# Main.net
KiCad netlist of a schematic drawn in Altium Designer
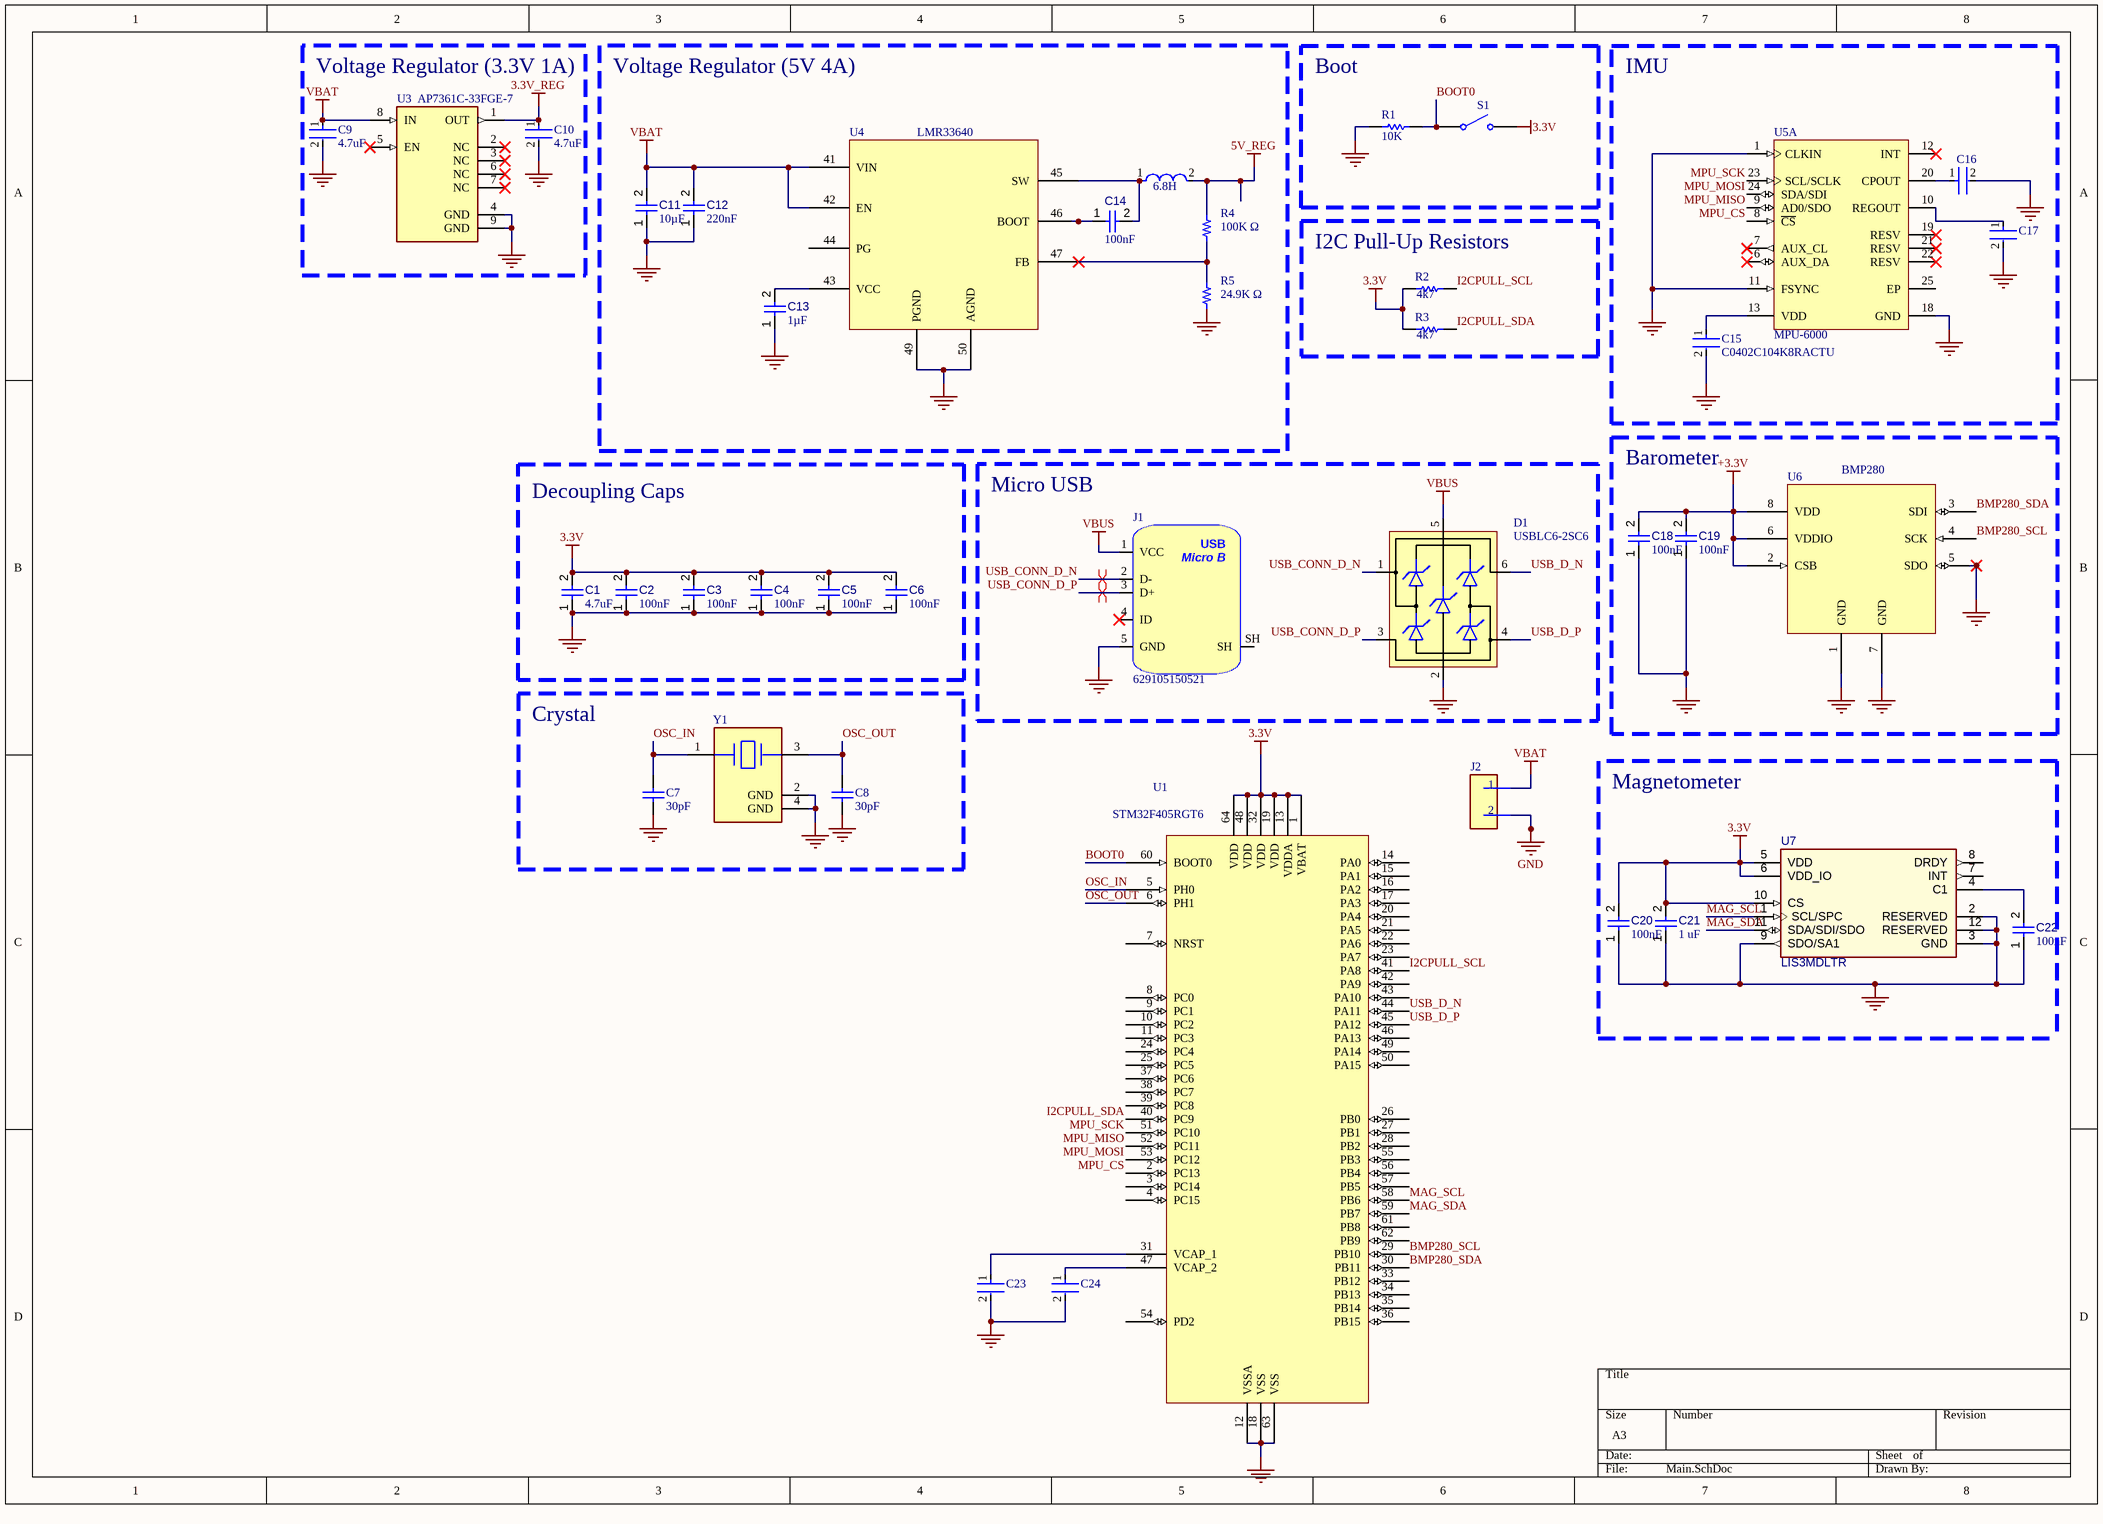
[diagram p0: Main.SchDoc]

(export (version "E")
  (design (tool "Eeschema 10.0.6"))
  (components
    (comp (ref "6.8H")
      (value "IHLP4040DZER6R8M01")
      (footprint "FP-IHLP-4040DZ-FP_3_124x3-MFG")
      (description "Commercial Inductors, High Saturation Series 6.8uH 8A 23.3mΩ 20%")
      (fields (field (name "TOLERANCE") "20%"))
      (libsource (lib "Altium Content Vault") (part "725321dda6339637d4d059423bc1c3c"))
    )
    (comp (ref "C1")
      (value "4.7uF")
      (footprint "CAPC1608X90X40NL10T20")
      (description "Chip Capacitor, 100 nF, +/- 10%, 50 V, 0603 (1608 Metric)")
      (fields (field (name "TOLERANCE") "10%") (field (name "Comment") "Capacitor 100 nF +/-10% 50 V 0603"))
      (libsource (lib "California Polytechnic University, Pomona") (part "CAP-NP-2"))
    )
    (comp (ref "C2")
      (value "100nF")
      (footprint "CAPC2013X95X50LL10T25")
      (description "Chip Capacitor, 100 nF, +/- 10%, 50 V, 0805 (2012 Metric)")
      (fields (field (name "TOLERANCE") "10%") (field (name "Comment") "Capacitor 100 nF +/-10% 50 V 0805"))
      (libsource (lib "California Polytechnic University, Pomona") (part "CAP-NP-2"))
    )
    (comp (ref "C3")
      (value "100nF")
      (footprint "CAPC2013X95X50LL10T25")
      (description "Chip Capacitor, 100 nF, +/- 10%, 50 V, 0805 (2012 Metric)")
      (fields (field (name "TOLERANCE") "10%") (field (name "Comment") "Capacitor 100 nF +/-10% 50 V 0805"))
      (libsource (lib "California Polytechnic University, Pomona") (part "CAP-NP-2"))
    )
    (comp (ref "C4")
      (value "100nF")
      (footprint "CAPC2013X95X50LL10T25")
      (description "Chip Capacitor, 100 nF, +/- 10%, 50 V, 0805 (2012 Metric)")
      (fields (field (name "TOLERANCE") "10%") (field (name "Comment") "Capacitor 100 nF +/-10% 50 V 0805"))
      (libsource (lib "California Polytechnic University, Pomona") (part "CAP-NP-2"))
    )
    (comp (ref "C5")
      (value "100nF")
      (footprint "CAPC2013X95X50LL10T25")
      (description "Chip Capacitor, 100 nF, +/- 10%, 50 V, 0805 (2012 Metric)")
      (fields (field (name "TOLERANCE") "10%") (field (name "Comment") "Capacitor 100 nF +/-10% 50 V 0805"))
      (libsource (lib "California Polytechnic University, Pomona") (part "CAP-NP-2"))
    )
    (comp (ref "C6")
      (value "100nF")
      (footprint "CAPC2013X95X50LL10T25")
      (description "Chip Capacitor, 100 nF, +/- 10%, 50 V, 0805 (2012 Metric)")
      (fields (field (name "TOLERANCE") "10%") (field (name "Comment") "Capacitor 100 nF +/-10% 50 V 0805"))
      (libsource (lib "California Polytechnic University, Pomona") (part "CAP-NP-2"))
    )
    (comp (ref "C7")
      (value "30pF")
      (footprint "CAPC1608X90X35NL10T15")
      (description "GRM1885C1H300JA01D")
      (fields (field (name "MANUFACTURER") "Murata"))
      (libsource (lib "Altium Content Vault") (part "CAP"))
    )
    (comp (ref "C8")
      (value "30pF")
      (footprint "CAPC1608X90X35NL10T15")
      (description "GRM1885C1H300JA01D")
      (fields (field (name "MANUFACTURER") "Murata"))
      (libsource (lib "Altium Content Vault") (part "CAP"))
    )
    (comp (ref "C9")
      (value "4.7uF")
      (footprint "FP-0805-L_2_01_0_2-W_1_25-IPC_A")
      (description "General Purpose Ceramic Capacitor, 0805, 4.7uF, 10%, X5R, 15%, 16V")
      (fields (field (name "TOLERANCE") "10%"))
      (libsource (lib "Altium Content Vault") (part "b4654b650e69147ec39a6b967a45e02"))
    )
    (comp (ref "C10")
      (value "4.7uF")
      (footprint "FP-0805-L_2_01_0_2-W_1_25-IPC_A")
      (description "General Purpose Ceramic Capacitor, 0805, 4.7uF, 10%, X5R, 15%, 16V")
      (fields (field (name "TOLERANCE") "10%"))
      (libsource (lib "Altium Content Vault") (part "b4654b650e69147ec39a6b967a45e02"))
    )
    (comp (ref "C11")
      (value "10µF")
      (footprint "CAPC0603(1608)100_L")
      (description "Chip Capacitor, 10µF +/-20%, 10V, 0603, Thickness 1 mm")
      (fields (field (name "TOLERANCE") "10%") (field (name "Comment") "Capacitor 10µF +/-20% 10V 0603"))
      (libsource (lib "California Polytechnic University, Pomona") (part "CAP-NP-2"))
    )
    (comp (ref "C12")
      (value "220nF")
      (footprint "CAPC0402(1005)60_L")
      (description "Chip Capacitor, 220nF +/-20%, 10V, 0402, Thickness 0.6 mm")
      (fields (field (name "TOLERANCE") "10%") (field (name "Comment") "Capacitor 220nF +/-20% 10V 0402"))
      (libsource (lib "California Polytechnic University, Pomona") (part "CAP-NP-2"))
    )
    (comp (ref "C13")
      (value "1µF")
      (footprint "CAPC1608X90X35ML15T15")
      (description "Chip Capacitor, 1 uF, +/- 10%, 16 V, 0603 (1608 Metric)")
      (fields (field (name "TOLERANCE") "10%") (field (name "Comment") "Capacitor 1uF +/- 10% 16V 0603"))
      (libsource (lib "California Polytechnic University, Pomona") (part "CAP-NP-2"))
    )
    (comp (ref "C14")
      (value "100nF")
      (footprint "CAPC1005X56X25LL10T15")
      (description "Chip Capacitor, 0.1 uF, +/- 5%, 16 V, 0402 (1005 Metric)")
      (fields (field (name "TOLERANCE") "5%") (field (name "Comment") "Capacitor 0.1 uF +/- 5% 16 V 0402"))
      (libsource (lib "California Polytechnic University, Pomona") (part "CAP-NP-2"))
    )
    (comp (ref "C15")
      (value "C0402C104K8RACTU")
      (footprint "FP-C0402-BB-MFG")
      (description "CAP CER 0.1UF 10V X7R 0402")
      (fields
        (field (name "OCTOPART") "https://octopart.com/c0402c104k8ractu-kemet-106349")
        (field (name "TOLERANCE") "0.1")
      )
      (libsource (lib "Altium Content Vault") (part "b4654b650e69147ec39a6b967a45e02"))
    )
    (comp (ref "C16")
      (value "06035C222KAT2A")
      (footprint "FP-0603-L_1_6_0_15-W_0_81-IPC_C")
      (description "General Purpose Ceramic Capacitor, 0603, 2.2nF, 10%, X7R, 15%, 50V")
      (fields (field (name "TOLERANCE") "10%") (field (name "VOLTAGE") "25V"))
      (libsource (lib "Altium Content Vault") (part "02cd4be3c70576c341d710602a673aa"))
    )
    (comp (ref "C17")
      (value "C0402C104K8RACTU")
      (footprint "FP-C0402-BB-MFG")
      (description "CAP CER 0.1UF 10V X7R 0402")
      (fields
        (field (name "OCTOPART") "https://octopart.com/c0402c104k8ractu-kemet-106349")
        (field (name "TOLERANCE") "0.1")
      )
      (libsource (lib "Altium Content Vault") (part "b4654b650e69147ec39a6b967a45e02"))
    )
    (comp (ref "C18")
      (value "100nF")
      (footprint "CAPC1005X56X25LL10T15")
      (description "Ceramic, X7R, +-10%, 2V")
      (fields (field (name "TOLERANCE") "5%") (field (name "Comment") "Capacitor 0.1 uF +/- 5% 16 V 0402"))
      (libsource (lib "California Polytechnic University, Pomona") (part "CAP-NP-2"))
    )
    (comp (ref "C19")
      (value "100nF")
      (footprint "CAPC1005X56X25LL10T15")
      (description "Ceramic, X7R, +-10%, 2V")
      (fields (field (name "TOLERANCE") "5%") (field (name "Comment") "Capacitor 0.1 uF +/- 5% 16 V 0402"))
      (libsource (lib "California Polytechnic University, Pomona") (part "CAP-NP-2"))
    )
    (comp (ref "C20")
      (value "100nF")
      (footprint "CAPC1005X56X25LL10T15")
      (description "Ceramic, X7R, +-10%, 2V")
      (fields (field (name "TOLERANCE") "5%") (field (name "Comment") "Capacitor 0.1 uF +/- 5% 16 V 0402"))
      (libsource (lib "California Polytechnic University, Pomona") (part "CAP-NP-2"))
    )
    (comp (ref "C21")
      (value "1 uF")
      (footprint "CAPC1005X56X25LL10T15")
      (description "Electrolytic Cap")
      (fields (field (name "TOLERANCE") "5%") (field (name "Comment") "Capacitor 0.1 uF +/- 5% 16 V 0402"))
      (libsource (lib "California Polytechnic University, Pomona") (part "CAP-NP-2"))
    )
    (comp (ref "C22")
      (value "100nF")
      (footprint "CAPC1005X56X25LL10T15")
      (description "Ceramic, X7R, +-10%, 2V")
      (fields (field (name "TOLERANCE") "5%") (field (name "Comment") "Capacitor 0.1 uF +/- 5% 16 V 0402"))
      (libsource (lib "California Polytechnic University, Pomona") (part "CAP-NP-2"))
    )
    (comp (ref "C23")
      (value "GCM21BR71A225KA37L")
      (footprint "FP-GCM21B-0_15-IPC_A")
      (description "Ceramic Capacitor for Automotive 2.2uF ±10% 10VDC X7R 0805 Embossed T/R")
      (fields (field (name "TOLERANCE") "10%") (field (name "VOLTAGE") "10V"))
      (libsource (lib "Altium Content Vault") (part "02cd4be3c70576c341d710602a673aa"))
    )
    (comp (ref "C24")
      (value "GCM21BR71A225KA37L")
      (footprint "FP-GCM21B-0_15-IPC_A")
      (description "Ceramic Capacitor for Automotive 2.2uF ±10% 10VDC X7R 0805 Embossed T/R")
      (fields (field (name "TOLERANCE") "10%") (field (name "VOLTAGE") "10V"))
      (libsource (lib "Altium Content Vault") (part "02cd4be3c70576c341d710602a673aa"))
    )
    (comp (ref "D1")
      (value "USBLC6-2SC6")
      (footprint "SOT-23-6")
      (description "Low-Capacitance ESD Protection USB")
      (fields (field (name "MANUFACTURER") "STMicroelectronics"))
      (libsource (lib "Schematic-Lib-PhilsLab") (part "USBLC6-2SC6"))
    )
    (comp (ref "J1")
      (value "629105150521")
      (footprint "629105150521")
      (description "USB Connector Type Micro B 2.0 SMD")
      (fields (field (name "MANUFACTURER") "Wurth"))
      (libsource (lib "Schematic-Lib-PhilsLab") (part "629105150521"))
    )
    (comp (ref "J2")
      (value "PRT-10474")
      (footprint "FP-PRT-10474-MFG")
      (description "XT60 CONNECTORS MALE/FEMALE PAIR")
      (libsource (lib "Altium Content Vault") (part "e9d95e9eb6564353a08a501d7ea6c79"))
    )
    (comp (ref "R1")
      (value "10K")
      (description "Resistor")
      (libsource (lib "Simulation Generic Components") (part "Resistor"))
    )
    (comp (ref "R2")
      (value "ERJ-P06J472V")
      (footprint "RESC2013X70X40LL20T20")
      (fields (field (name "MANUFACTURER") "Panasonic"))
      (libsource (lib "Altium Content Vault") (part "RES"))
    )
    (comp (ref "R3")
      (value "ERJ-P06J472V")
      (footprint "RESC2013X70X40LL20T20")
      (fields (field (name "MANUFACTURER") "Panasonic"))
      (libsource (lib "Altium Content Vault") (part "RES"))
    )
    (comp (ref "R4") (value "100K Ω") (libsource (lib "Schlib1") (part "RCS0603100KFKEA")))
    (comp (ref "R5") (value "24.9K Ω") (libsource (lib "Schlib1") (part "RCS0603100KFKEA")))
    (comp (ref "S1")
      (value "Single-Pole, Single-Throw Switch")
      (libsource (lib "Simulation Generic Components") (part "SPST SW"))
    )
    (comp (ref "U1")
      (value "STM32F405RGT6")
      (description "MCU")
      (libsource (lib "Schlib1") (part "STM32F405RGT6"))
    )
    (comp (ref "U3")
      (value "AP7361C-33FGE-7")
      (footprint "FP-U-DFN3030-8_Type_E-MFG")
      (description "IC REG LINEAR 3.3V 1A UDFN3030-8")
      (fields
        (field (name "MANUFACTURER") "Diodes Inc.")
        (field (name "OCTOPART") "https://octopart.com/ap7361c-33fge-7-diodes+inc.-65869522")
      )
      (libsource (lib "Altium Content Vault") (part "2971fe8480f7e8815ea3c3920f93e3e"))
    )
    (comp (ref "U4") (value "LMR33640") (libsource (lib "Schlib1") (part "LMR33640")))
    (comp (ref "U5")
      (value "MPU-6000")
      (footprint "INSE-QFN-24_V")
      (fields (field (name "MANUFACTURER") "InvenSense"))
      (libsource (lib "Altium Content Vault") (part "INSE-MPU-6000"))
    )
    (comp (ref "U6") (value "BMP280") (libsource (lib "Schlib1") (part "BMP280")))
    (comp (ref "U7")
      (value "LIS3MDLTR")
      (footprint "STM-LGA-12")
      (description "Digital Output Magnetic Sensor, 1.9 to 3.6 V, -40 to 85 degC, 12-Pin LGA, RoHS, Tape and Reel")
      (libsource (lib "California Polytechnic University, Pomona") (part "CMP-00084-7"))
    )
    (comp (ref "Y1")
      (value "ABM8-16.000MHZ-B2-T")
      (footprint "FP-ABM8-MFG")
      (description "Crystal 16MHz ±20ppm 18pF SMD-4 3.2mm x 2.5mm")
      (fields (field (name "TOLERANCE") "20ppm"))
      (libsource (lib "Altium Content Vault") (part "dfdb7f9a12507849fb681da9a70121c"))
    )
  )
  (nets
    (net (code "1") (name "+3.3V") (class "Default")
      (node (ref "C18") (pin "2") (pinfunction "2_2") (pintype "passive"))
      (node (ref "C19") (pin "2") (pinfunction "2_2") (pintype "passive"))
      (node (ref "U6") (pin "2") (pinfunction "CSB_2") (pintype "input"))
      (node (ref "U6") (pin "6") (pinfunction "VDDIO_6") (pintype "power_in"))
      (node (ref "U6") (pin "8") (pinfunction "VDD_8") (pintype "power_in"))
    )
    (net (code "2") (name "/BMP280_SCL") (class "Default")
      (node (ref "U1") (pin "29") (pinfunction "PB10_29") (pintype "bidirectional"))
      (node (ref "U6") (pin "4") (pinfunction "SCK_4") (pintype "input"))
    )
    (net (code "3") (name "/BMP280_SDA") (class "Default")
      (node (ref "U1") (pin "30") (pinfunction "PB11_30") (pintype "bidirectional"))
      (node (ref "U6") (pin "3") (pinfunction "SDI_3") (pintype "bidirectional"))
    )
    (net (code "4") (name "/BOOT0") (class "Default")
      (node (ref "R1") (pin "1") (pinfunction "1_1") (pintype "passive"))
      (node (ref "S1") (pin "1") (pinfunction "1_1") (pintype "passive"))
      (node (ref "U1") (pin "60") (pinfunction "BOOT0_60") (pintype "input"))
    )
    (net (code "5") (name "/I2CPULL_SCL") (class "Default")
      (node (ref "R2") (pin "2") (pinfunction "2_2") (pintype "passive"))
      (node (ref "U1") (pin "41") (pinfunction "PA8_41") (pintype "bidirectional"))
    )
    (net (code "6") (name "/I2CPULL_SDA") (class "Default")
      (node (ref "R3") (pin "2") (pinfunction "2_2") (pintype "passive"))
      (node (ref "U1") (pin "40") (pinfunction "PC9_40") (pintype "bidirectional"))
    )
    (net (code "7") (name "/MAG_SCL") (class "Default")
      (node (ref "U1") (pin "58") (pinfunction "PB6_58") (pintype "bidirectional"))
      (node (ref "U7") (pin "1") (pinfunction "SCL/SPC_1") (pintype "input"))
    )
    (net (code "8") (name "/MAG_SDA") (class "Default")
      (node (ref "U1") (pin "59") (pinfunction "PB7_59") (pintype "bidirectional"))
      (node (ref "U7") (pin "11") (pinfunction "SDA/SDI/SDO_11") (pintype "bidirectional"))
    )
    (net (code "9") (name "/MPU_CS") (class "Default")
      (node (ref "U1") (pin "2") (pinfunction "PC13_2") (pintype "bidirectional"))
      (node (ref "U5") (pin "8") (pinfunction "~{CS}_8") (pintype "input"))
    )
    (net (code "10") (name "/MPU_MISO") (class "Default")
      (node (ref "U1") (pin "52") (pinfunction "PC11_52") (pintype "bidirectional"))
      (node (ref "U5") (pin "9") (pinfunction "AD0/SDO_9") (pintype "bidirectional"))
    )
    (net (code "11") (name "/MPU_MOSI") (class "Default")
      (node (ref "U1") (pin "53") (pinfunction "PC12_53") (pintype "bidirectional"))
      (node (ref "U5") (pin "24") (pinfunction "SDA/SDI_24") (pintype "bidirectional"))
    )
    (net (code "12") (name "/MPU_SCK") (class "Default")
      (node (ref "U1") (pin "51") (pinfunction "PC10_51") (pintype "bidirectional"))
      (node (ref "U5") (pin "23") (pinfunction "SCL/SCLK_23") (pintype "input"))
    )
    (net (code "13") (name "/OSC_IN") (class "Default")
      (node (ref "C7") (pin "2") (pinfunction "2_2") (pintype "passive"))
      (node (ref "U1") (pin "5") (pinfunction "PH0_5") (pintype "input"))
      (node (ref "Y1") (pin "1") (pinfunction "1_1") (pintype "passive"))
    )
    (net (code "14") (name "/OSC_OUT") (class "Default")
      (node (ref "C8") (pin "2") (pinfunction "2_2") (pintype "passive"))
      (node (ref "U1") (pin "6") (pinfunction "PH1_6") (pintype "bidirectional"))
      (node (ref "Y1") (pin "3") (pinfunction "3_3") (pintype "passive"))
    )
    (net (code "15") (name "/USB_CONN_D_N") (class "Default")
      (node (ref "D1") (pin "1") (pinfunction "IO1_1") (pintype "bidirectional"))
      (node (ref "J1") (pin "2") (pinfunction "D-_2") (pintype "passive"))
    )
    (net (code "16") (name "/USB_CONN_D_P") (class "Default")
      (node (ref "D1") (pin "3") (pinfunction "IO2_3") (pintype "bidirectional"))
      (node (ref "J1") (pin "3") (pinfunction "D+_3") (pintype "passive"))
    )
    (net (code "17") (name "/USB_D_N") (class "Default")
      (node (ref "D1") (pin "6") (pinfunction "IO1_6") (pintype "bidirectional"))
      (node (ref "U1") (pin "44") (pinfunction "PA11_44") (pintype "bidirectional"))
    )
    (net (code "18") (name "/USB_D_P") (class "Default")
      (node (ref "D1") (pin "4") (pinfunction "IO2_4") (pintype "bidirectional"))
      (node (ref "U1") (pin "45") (pinfunction "PA12_45") (pintype "bidirectional"))
    )
    (net (code "19") (name "3.3V") (class "Default")
      (node (ref "C1") (pin "2") (pinfunction "2_2") (pintype "passive"))
      (node (ref "C2") (pin "2") (pinfunction "2_2") (pintype "passive"))
      (node (ref "C20") (pin "2") (pinfunction "2_2") (pintype "passive"))
      (node (ref "C21") (pin "2") (pinfunction "2_2") (pintype "passive"))
      (node (ref "C3") (pin "2") (pinfunction "2_2") (pintype "passive"))
      (node (ref "C4") (pin "2") (pinfunction "2_2") (pintype "passive"))
      (node (ref "C5") (pin "2") (pinfunction "2_2") (pintype "passive"))
      (node (ref "C6") (pin "2") (pinfunction "2_2") (pintype "passive"))
      (node (ref "R2") (pin "1") (pinfunction "1_1") (pintype "passive"))
      (node (ref "R3") (pin "1") (pinfunction "1_1") (pintype "passive"))
      (node (ref "S1") (pin "2") (pinfunction "2_2") (pintype "passive"))
      (node (ref "U1") (pin "1") (pinfunction "VBAT_1") (pintype "power_in"))
      (node (ref "U1") (pin "13") (pinfunction "VDDA_13") (pintype "power_in"))
      (node (ref "U1") (pin "19") (pinfunction "VDD_19") (pintype "power_in"))
      (node (ref "U1") (pin "32") (pinfunction "VDD_32") (pintype "power_in"))
      (node (ref "U1") (pin "48") (pinfunction "VDD_48") (pintype "power_in"))
      (node (ref "U1") (pin "64") (pinfunction "VDD_64") (pintype "power_in"))
      (node (ref "U7") (pin "10") (pinfunction "CS_10") (pintype "input"))
      (node (ref "U7") (pin "5") (pinfunction "VDD_5") (pintype "power_in"))
      (node (ref "U7") (pin "6") (pinfunction "VDD_IO_6") (pintype "power_in"))
    )
    (net (code "20") (name "3.3V_REG") (class "Default")
      (node (ref "C10") (pin "1") (pinfunction "1_1") (pintype "passive"))
      (node (ref "U3") (pin "1") (pinfunction "OUT_1") (pintype "output"))
    )
    (net (code "21") (name "5V_REG") (class "Default")
      (node (ref "6.8H") (pin "2") (pinfunction "2_2") (pintype "passive"))
    )
    (net (code "22") (name "GND") (class "Default")
      (node (ref "C1") (pin "1") (pinfunction "1_1") (pintype "passive"))
      (node (ref "C10") (pin "2") (pinfunction "2_2") (pintype "passive"))
      (node (ref "C11") (pin "1") (pinfunction "1_1") (pintype "passive"))
      (node (ref "C12") (pin "1") (pinfunction "1_1") (pintype "passive"))
      (node (ref "C13") (pin "1") (pinfunction "1_1") (pintype "passive"))
      (node (ref "C15") (pin "2") (pinfunction "2_2") (pintype "passive"))
      (node (ref "C16") (pin "2") (pinfunction "2_2") (pintype "passive"))
      (node (ref "C17") (pin "2") (pinfunction "2_2") (pintype "passive"))
      (node (ref "C18") (pin "1") (pinfunction "1_1") (pintype "passive"))
      (node (ref "C19") (pin "1") (pinfunction "1_1") (pintype "passive"))
      (node (ref "C2") (pin "1") (pinfunction "1_1") (pintype "passive"))
      (node (ref "C20") (pin "1") (pinfunction "1_1") (pintype "passive"))
      (node (ref "C21") (pin "1") (pinfunction "1_1") (pintype "passive"))
      (node (ref "C22") (pin "1") (pinfunction "1_1") (pintype "passive"))
      (node (ref "C23") (pin "2") (pinfunction "2_2") (pintype "passive"))
      (node (ref "C24") (pin "2") (pinfunction "2_2") (pintype "passive"))
      (node (ref "C3") (pin "1") (pinfunction "1_1") (pintype "passive"))
      (node (ref "C4") (pin "1") (pinfunction "1_1") (pintype "passive"))
      (node (ref "C5") (pin "1") (pinfunction "1_1") (pintype "passive"))
      (node (ref "C6") (pin "1") (pinfunction "1_1") (pintype "passive"))
      (node (ref "C7") (pin "1") (pinfunction "1_1") (pintype "passive"))
      (node (ref "C8") (pin "1") (pinfunction "1_1") (pintype "passive"))
      (node (ref "C9") (pin "2") (pinfunction "2_2") (pintype "passive"))
      (node (ref "D1") (pin "2") (pinfunction "GND_2") (pintype "power_in"))
      (node (ref "J1") (pin "5") (pinfunction "GND_5") (pintype "passive"))
      (node (ref "R1") (pin "2") (pinfunction "2_2") (pintype "passive"))
      (node (ref "U1") (pin "12") (pinfunction "VSSA_12") (pintype "power_in"))
      (node (ref "U1") (pin "18") (pinfunction "VSS_18") (pintype "power_in"))
      (node (ref "U1") (pin "63") (pinfunction "VSS_63") (pintype "power_in"))
      (node (ref "U3") (pin "4") (pinfunction "GND_4") (pintype "power_in"))
      (node (ref "U3") (pin "9") (pinfunction "GND_9") (pintype "power_in"))
      (node (ref "U4") (pin "49") (pinfunction "PGND_49") (pintype "passive"))
      (node (ref "U4") (pin "50") (pinfunction "AGND_50") (pintype "passive"))
      (node (ref "U5") (pin "1") (pinfunction "CLKIN_1") (pintype "input"))
      (node (ref "U5") (pin "11") (pinfunction "FSYNC_11") (pintype "input"))
      (node (ref "U5") (pin "18") (pinfunction "GND_18") (pintype "power_in"))
      (node (ref "U6") (pin "1") (pinfunction "GND_1") (pintype "power_in"))
      (node (ref "U6") (pin "5") (pinfunction "SDO_5") (pintype "bidirectional"))
      (node (ref "U6") (pin "7") (pinfunction "GND_7") (pintype "power_in"))
      (node (ref "U7") (pin "12") (pinfunction "RESERVED_12") (pintype "passive"))
      (node (ref "U7") (pin "2") (pinfunction "RESERVED_2") (pintype "passive"))
      (node (ref "U7") (pin "3") (pinfunction "GND_3") (pintype "power_in"))
      (node (ref "U7") (pin "9") (pinfunction "SDO/SA1_9") (pintype "output"))
      (node (ref "Y1") (pin "2") (pinfunction "GND_2") (pintype "power_in"))
      (node (ref "Y1") (pin "4") (pinfunction "GND_4") (pintype "power_in"))
    )
    (net (code "23") (name "Net-(U1-VCAP_1)") (class "Default")
      (node (ref "C23") (pin "1") (pinfunction "1_1") (pintype "passive"))
      (node (ref "U1") (pin "31") (pinfunction "VCAP_1_31") (pintype "power_in"))
    )
    (net (code "24") (name "Net-(U1-VCAP_2)") (class "Default")
      (node (ref "C24") (pin "1") (pinfunction "1_1") (pintype "passive"))
      (node (ref "U1") (pin "47") (pinfunction "VCAP_2_47") (pintype "power_in"))
    )
    (net (code "25") (name "Net-(U4-BOOT)") (class "Default")
      (node (ref "C14") (pin "1") (pinfunction "1_1") (pintype "passive"))
      (node (ref "U4") (pin "46") (pinfunction "BOOT_46") (pintype "passive"))
    )
    (net (code "26") (name "Net-(U4-SW)") (class "Default")
      (node (ref "6.8H") (pin "1") (pinfunction "1_1") (pintype "passive"))
      (node (ref "C14") (pin "2") (pinfunction "2_2") (pintype "passive"))
      (node (ref "U4") (pin "45") (pinfunction "SW_45") (pintype "passive"))
    )
    (net (code "27") (name "Net-(U4-VCC)") (class "Default")
      (node (ref "C13") (pin "2") (pinfunction "2_2") (pintype "passive"))
      (node (ref "U4") (pin "43") (pinfunction "VCC_43") (pintype "passive"))
    )
    (net (code "28") (name "Net-(U5A-CPOUT)") (class "Default")
      (node (ref "C16") (pin "1") (pinfunction "1_1") (pintype "passive"))
      (node (ref "U5") (pin "20") (pinfunction "CPOUT_20") (pintype "passive"))
    )
    (net (code "29") (name "Net-(U5A-REGOUT)") (class "Default")
      (node (ref "C17") (pin "1") (pinfunction "1_1") (pintype "passive"))
      (node (ref "U5") (pin "10") (pinfunction "REGOUT_10") (pintype "passive"))
    )
    (net (code "30") (name "Net-(U5A-VDD)") (class "Default")
      (node (ref "C15") (pin "1") (pinfunction "1_1") (pintype "passive"))
      (node (ref "U5") (pin "13") (pinfunction "VDD_13") (pintype "power_in"))
    )
    (net (code "31") (name "Net-(U7-C1)") (class "Default")
      (node (ref "C22") (pin "2") (pinfunction "2_2") (pintype "passive"))
      (node (ref "U7") (pin "4") (pinfunction "C1_4") (pintype "passive"))
    )
    (net (code "32") (name "VBAT") (class "Default")
      (node (ref "C11") (pin "2") (pinfunction "2_2") (pintype "passive"))
      (node (ref "C12") (pin "2") (pinfunction "2_2") (pintype "passive"))
      (node (ref "C9") (pin "1") (pinfunction "1_1") (pintype "passive"))
      (node (ref "U3") (pin "8") (pinfunction "IN_8") (pintype "input"))
      (node (ref "U4") (pin "41") (pinfunction "VIN_41") (pintype "passive"))
      (node (ref "U4") (pin "42") (pinfunction "EN_42") (pintype "passive"))
    )
    (net (code "33") (name "VBUS") (class "Default")
      (node (ref "D1") (pin "5") (pinfunction "VBUS_5") (pintype "power_in"))
      (node (ref "J1") (pin "1") (pinfunction "VCC_1") (pintype "passive"))
    )
    (net (code "34") (name "unconnected-(J1-ID-Pad4)") (class "Default")
      (node (ref "J1") (pin "4") (pinfunction "ID_4") (pintype "passive+no_connect"))
    )
    (net (code "35") (name "unconnected-(J1-PadSH)") (class "Default")
      (node (ref "J1") (pin "SH") (pinfunction "SH_SH") (pintype "passive"))
    )
    (net (code "36") (name "unconnected-(U1-NRST-Pad7)") (class "Default")
      (node (ref "U1") (pin "7") (pinfunction "NRST_7") (pintype "bidirectional"))
    )
    (net (code "37") (name "unconnected-(U1-PA0-Pad14)") (class "Default")
      (node (ref "U1") (pin "14") (pinfunction "PA0_14") (pintype "bidirectional"))
    )
    (net (code "38") (name "unconnected-(U1-PA1-Pad15)") (class "Default")
      (node (ref "U1") (pin "15") (pinfunction "PA1_15") (pintype "bidirectional"))
    )
    (net (code "39") (name "unconnected-(U1-PA2-Pad16)") (class "Default")
      (node (ref "U1") (pin "16") (pinfunction "PA2_16") (pintype "bidirectional"))
    )
    (net (code "40") (name "unconnected-(U1-PA3-Pad17)") (class "Default")
      (node (ref "U1") (pin "17") (pinfunction "PA3_17") (pintype "bidirectional"))
    )
    (net (code "41") (name "unconnected-(U1-PA4-Pad20)") (class "Default")
      (node (ref "U1") (pin "20") (pinfunction "PA4_20") (pintype "bidirectional"))
    )
    (net (code "42") (name "unconnected-(U1-PA5-Pad21)") (class "Default")
      (node (ref "U1") (pin "21") (pinfunction "PA5_21") (pintype "bidirectional"))
    )
    (net (code "43") (name "unconnected-(U1-PA6-Pad22)") (class "Default")
      (node (ref "U1") (pin "22") (pinfunction "PA6_22") (pintype "bidirectional"))
    )
    (net (code "44") (name "unconnected-(U1-PA7-Pad23)") (class "Default")
      (node (ref "U1") (pin "23") (pinfunction "PA7_23") (pintype "bidirectional"))
    )
    (net (code "45") (name "unconnected-(U1-PA9-Pad42)") (class "Default")
      (node (ref "U1") (pin "42") (pinfunction "PA9_42") (pintype "bidirectional"))
    )
    (net (code "46") (name "unconnected-(U1-PA10-Pad43)") (class "Default")
      (node (ref "U1") (pin "43") (pinfunction "PA10_43") (pintype "bidirectional"))
    )
    (net (code "47") (name "unconnected-(U1-PA13-Pad46)") (class "Default")
      (node (ref "U1") (pin "46") (pinfunction "PA13_46") (pintype "bidirectional"))
    )
    (net (code "48") (name "unconnected-(U1-PA14-Pad49)") (class "Default")
      (node (ref "U1") (pin "49") (pinfunction "PA14_49") (pintype "bidirectional"))
    )
    (net (code "49") (name "unconnected-(U1-PA15-Pad50)") (class "Default")
      (node (ref "U1") (pin "50") (pinfunction "PA15_50") (pintype "bidirectional"))
    )
    (net (code "50") (name "unconnected-(U1-PB0-Pad26)") (class "Default")
      (node (ref "U1") (pin "26") (pinfunction "PB0_26") (pintype "bidirectional"))
    )
    (net (code "51") (name "unconnected-(U1-PB1-Pad27)") (class "Default")
      (node (ref "U1") (pin "27") (pinfunction "PB1_27") (pintype "bidirectional"))
    )
    (net (code "52") (name "unconnected-(U1-PB2-Pad28)") (class "Default")
      (node (ref "U1") (pin "28") (pinfunction "PB2_28") (pintype "bidirectional"))
    )
    (net (code "53") (name "unconnected-(U1-PB3-Pad55)") (class "Default")
      (node (ref "U1") (pin "55") (pinfunction "PB3_55") (pintype "bidirectional"))
    )
    (net (code "54") (name "unconnected-(U1-PB4-Pad56)") (class "Default")
      (node (ref "U1") (pin "56") (pinfunction "PB4_56") (pintype "bidirectional"))
    )
    (net (code "55") (name "unconnected-(U1-PB5-Pad57)") (class "Default")
      (node (ref "U1") (pin "57") (pinfunction "PB5_57") (pintype "bidirectional"))
    )
    (net (code "56") (name "unconnected-(U1-PB8-Pad61)") (class "Default")
      (node (ref "U1") (pin "61") (pinfunction "PB8_61") (pintype "bidirectional"))
    )
    (net (code "57") (name "unconnected-(U1-PB9-Pad62)") (class "Default")
      (node (ref "U1") (pin "62") (pinfunction "PB9_62") (pintype "bidirectional"))
    )
    (net (code "58") (name "unconnected-(U1-PB12-Pad33)") (class "Default")
      (node (ref "U1") (pin "33") (pinfunction "PB12_33") (pintype "bidirectional"))
    )
    (net (code "59") (name "unconnected-(U1-PB13-Pad34)") (class "Default")
      (node (ref "U1") (pin "34") (pinfunction "PB13_34") (pintype "bidirectional"))
    )
    (net (code "60") (name "unconnected-(U1-PB14-Pad35)") (class "Default")
      (node (ref "U1") (pin "35") (pinfunction "PB14_35") (pintype "bidirectional"))
    )
    (net (code "61") (name "unconnected-(U1-PB15-Pad36)") (class "Default")
      (node (ref "U1") (pin "36") (pinfunction "PB15_36") (pintype "bidirectional"))
    )
    (net (code "62") (name "unconnected-(U1-PC0-Pad8)") (class "Default")
      (node (ref "U1") (pin "8") (pinfunction "PC0_8") (pintype "bidirectional"))
    )
    (net (code "63") (name "unconnected-(U1-PC1-Pad9)") (class "Default")
      (node (ref "U1") (pin "9") (pinfunction "PC1_9") (pintype "bidirectional"))
    )
    (net (code "64") (name "unconnected-(U1-PC2-Pad10)") (class "Default")
      (node (ref "U1") (pin "10") (pinfunction "PC2_10") (pintype "bidirectional"))
    )
    (net (code "65") (name "unconnected-(U1-PC3-Pad11)") (class "Default")
      (node (ref "U1") (pin "11") (pinfunction "PC3_11") (pintype "bidirectional"))
    )
    (net (code "66") (name "unconnected-(U1-PC4-Pad24)") (class "Default")
      (node (ref "U1") (pin "24") (pinfunction "PC4_24") (pintype "bidirectional"))
    )
    (net (code "67") (name "unconnected-(U1-PC5-Pad25)") (class "Default")
      (node (ref "U1") (pin "25") (pinfunction "PC5_25") (pintype "bidirectional"))
    )
    (net (code "68") (name "unconnected-(U1-PC6-Pad37)") (class "Default")
      (node (ref "U1") (pin "37") (pinfunction "PC6_37") (pintype "bidirectional"))
    )
    (net (code "69") (name "unconnected-(U1-PC7-Pad38)") (class "Default")
      (node (ref "U1") (pin "38") (pinfunction "PC7_38") (pintype "bidirectional"))
    )
    (net (code "70") (name "unconnected-(U1-PC8-Pad39)") (class "Default")
      (node (ref "U1") (pin "39") (pinfunction "PC8_39") (pintype "bidirectional"))
    )
    (net (code "71") (name "unconnected-(U1-PC14-Pad3)") (class "Default")
      (node (ref "U1") (pin "3") (pinfunction "PC14_3") (pintype "bidirectional"))
    )
    (net (code "72") (name "unconnected-(U1-PC15-Pad4)") (class "Default")
      (node (ref "U1") (pin "4") (pinfunction "PC15_4") (pintype "bidirectional"))
    )
    (net (code "73") (name "unconnected-(U1-PD2-Pad54)") (class "Default")
      (node (ref "U1") (pin "54") (pinfunction "PD2_54") (pintype "bidirectional"))
    )
    (net (code "74") (name "unconnected-(U3-EN-Pad5)") (class "Default")
      (node (ref "U3") (pin "5") (pinfunction "EN_5") (pintype "input+no_connect"))
    )
    (net (code "75") (name "unconnected-(U3-NC-Pad2)") (class "Default")
      (node (ref "U3") (pin "2") (pinfunction "NC_2") (pintype "passive+no_connect"))
    )
    (net (code "76") (name "unconnected-(U3-NC-Pad3)") (class "Default")
      (node (ref "U3") (pin "3") (pinfunction "NC_3") (pintype "passive+no_connect"))
    )
    (net (code "77") (name "unconnected-(U3-NC-Pad6)") (class "Default")
      (node (ref "U3") (pin "6") (pinfunction "NC_6") (pintype "passive+no_connect"))
    )
    (net (code "78") (name "unconnected-(U3-NC-Pad7)") (class "Default")
      (node (ref "U3") (pin "7") (pinfunction "NC_7") (pintype "passive+no_connect"))
    )
    (net (code "79") (name "unconnected-(U4-FB-Pad47)") (class "Default")
      (node (ref "U4") (pin "47") (pinfunction "FB_47") (pintype "passive+no_connect"))
    )
    (net (code "80") (name "unconnected-(U4-PG-Pad44)") (class "Default")
      (node (ref "U4") (pin "44") (pinfunction "PG_44") (pintype "passive"))
    )
    (net (code "81") (name "unconnected-(U5A-AUX_CL-Pad7)") (class "Default")
      (node (ref "U5") (pin "7") (pinfunction "AUX_CL_7") (pintype "output+no_connect"))
    )
    (net (code "82") (name "unconnected-(U5A-AUX_DA-Pad6)") (class "Default")
      (node (ref "U5") (pin "6") (pinfunction "AUX_DA_6") (pintype "bidirectional+no_connect"))
    )
    (net (code "83") (name "unconnected-(U5A-EP-Pad25)") (class "Default")
      (node (ref "U5") (pin "25") (pinfunction "EP_25") (pintype "passive"))
    )
    (net (code "84") (name "unconnected-(U5A-INT-Pad12)") (class "Default")
      (node (ref "U5") (pin "12") (pinfunction "INT_12") (pintype "open_collector+no_connect"))
    )
    (net (code "85") (name "unconnected-(U5A-RESV-Pad19)") (class "Default")
      (node (ref "U5") (pin "19") (pinfunction "RESV_19") (pintype "passive+no_connect"))
    )
    (net (code "86") (name "unconnected-(U5A-RESV-Pad21)") (class "Default")
      (node (ref "U5") (pin "21") (pinfunction "RESV_21") (pintype "passive+no_connect"))
    )
    (net (code "87") (name "unconnected-(U5A-RESV-Pad22)") (class "Default")
      (node (ref "U5") (pin "22") (pinfunction "RESV_22") (pintype "passive+no_connect"))
    )
    (net (code "88") (name "unconnected-(U7-DRDY-Pad8)") (class "Default")
      (node (ref "U7") (pin "8") (pinfunction "DRDY_8") (pintype "output"))
    )
    (net (code "89") (name "unconnected-(U7-INT-Pad7)") (class "Default")
      (node (ref "U7") (pin "7") (pinfunction "INT_7") (pintype "output"))
    )
  )
)
